# display-schematics.net
KiCad netlist of a schematic drawn in EAGLE
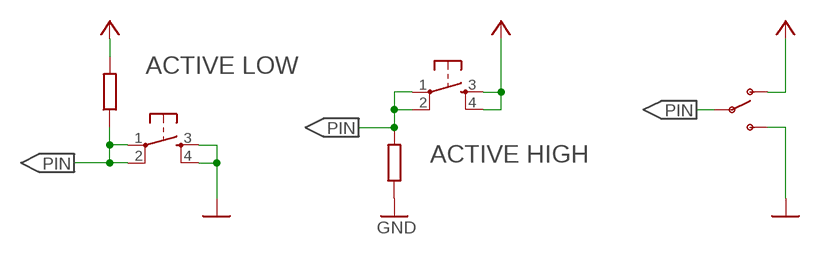
[diagram p0: schematic, sheet 1]
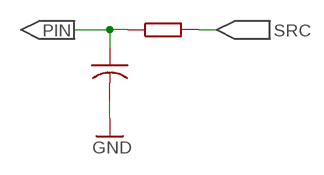
[diagram p1: schematic, sheet 2]

(export (version "E")
  (design (tool "Eeschema 10.0.6"))
  (components
    (comp (ref "R1")
      (value "R-EU_0411/15")
      (footprint "eagle-import:0411_15")
      (libsource (lib "eagle-import") (part "R-EU_0411/15"))
    )
    (comp (ref "R2")
      (value "R-EU_0411/15")
      (footprint "eagle-import:0411_15")
      (libsource (lib "eagle-import") (part "R-EU_0411/15"))
    )
    (comp (ref "S1")
      (value "SWITCH-SPDTSMD2")
      (footprint "eagle-import:SWITCH-SPDT-SMD")
      (libsource (lib "eagle-import") (part "SWITCH-SPDTSMD2"))
    )
    (comp (ref "S2")
      (value "TAC_SWITCHPTH")
      (footprint "eagle-import:TACTILE-PTH")
      (libsource (lib "eagle-import") (part "TAC_SWITCHPTH"))
    )
    (comp (ref "S3")
      (value "TAC_SWITCHPTH")
      (footprint "eagle-import:TACTILE-PTH")
      (libsource (lib "eagle-import") (part "TAC_SWITCHPTH"))
    )
    (comp (ref "C1")
      (value "C-US025-040X050")
      (footprint "eagle-import:C025-040X050")
      (libsource (lib "eagle-import") (part "C-US025-040X050"))
    )
    (comp (ref "R3")
      (value "R-EU_0411/15")
      (footprint "eagle-import:0411_15")
      (libsource (lib "eagle-import") (part "R-EU_0411/15"))
    )
  )
  (nets
    (net (code "1") (name "GND") (class "Default")
      (node (ref "C1") (pin "2") (pinfunction "2_2") (pintype "passive"))
      (node (ref "R2") (pin "1") (pinfunction "1_1") (pintype "passive"))
      (node (ref "S1") (pin "3") (pinfunction "S_3") (pintype "passive"))
      (node (ref "S2") (pin "3") (pinfunction "3_3") (pintype "passive"))
      (node (ref "S2") (pin "4") (pinfunction "4_4") (pintype "passive"))
    )
    (net (code "2") (name "Net-(C1-Pad1)") (class "Default")
      (node (ref "C1") (pin "1") (pinfunction "1_1") (pintype "passive"))
      (node (ref "R3") (pin "1") (pinfunction "1_1") (pintype "passive"))
    )
    (net (code "3") (name "Net-(R1-Pad1)") (class "Default")
      (node (ref "R1") (pin "1") (pinfunction "1_1") (pintype "passive"))
      (node (ref "S2") (pin "1") (pinfunction "1_1") (pintype "passive"))
      (node (ref "S2") (pin "2") (pinfunction "2_2") (pintype "passive"))
    )
    (net (code "4") (name "Net-(R2-Pad2)") (class "Default")
      (node (ref "R2") (pin "2") (pinfunction "2_2") (pintype "passive"))
      (node (ref "S3") (pin "1") (pinfunction "1_1") (pintype "passive"))
      (node (ref "S3") (pin "2") (pinfunction "2_2") (pintype "passive"))
    )
    (net (code "5") (name "VCC") (class "Default")
      (node (ref "R1") (pin "2") (pinfunction "2_2") (pintype "passive"))
      (node (ref "S1") (pin "1") (pinfunction "O_1") (pintype "passive"))
      (node (ref "S3") (pin "3") (pinfunction "3_3") (pintype "passive"))
      (node (ref "S3") (pin "4") (pinfunction "4_4") (pintype "passive"))
    )
    (net (code "6") (name "unconnected-(R3-Pad2)") (class "Default")
      (node (ref "R3") (pin "2") (pinfunction "2_2") (pintype "passive"))
    )
    (net (code "7") (name "unconnected-(S1-P-Pad2)") (class "Default")
      (node (ref "S1") (pin "2") (pinfunction "P_2") (pintype "passive"))
    )
  )
)
